# quantizer_control.net
KiCad netlist of a schematic drawn in EAGLE
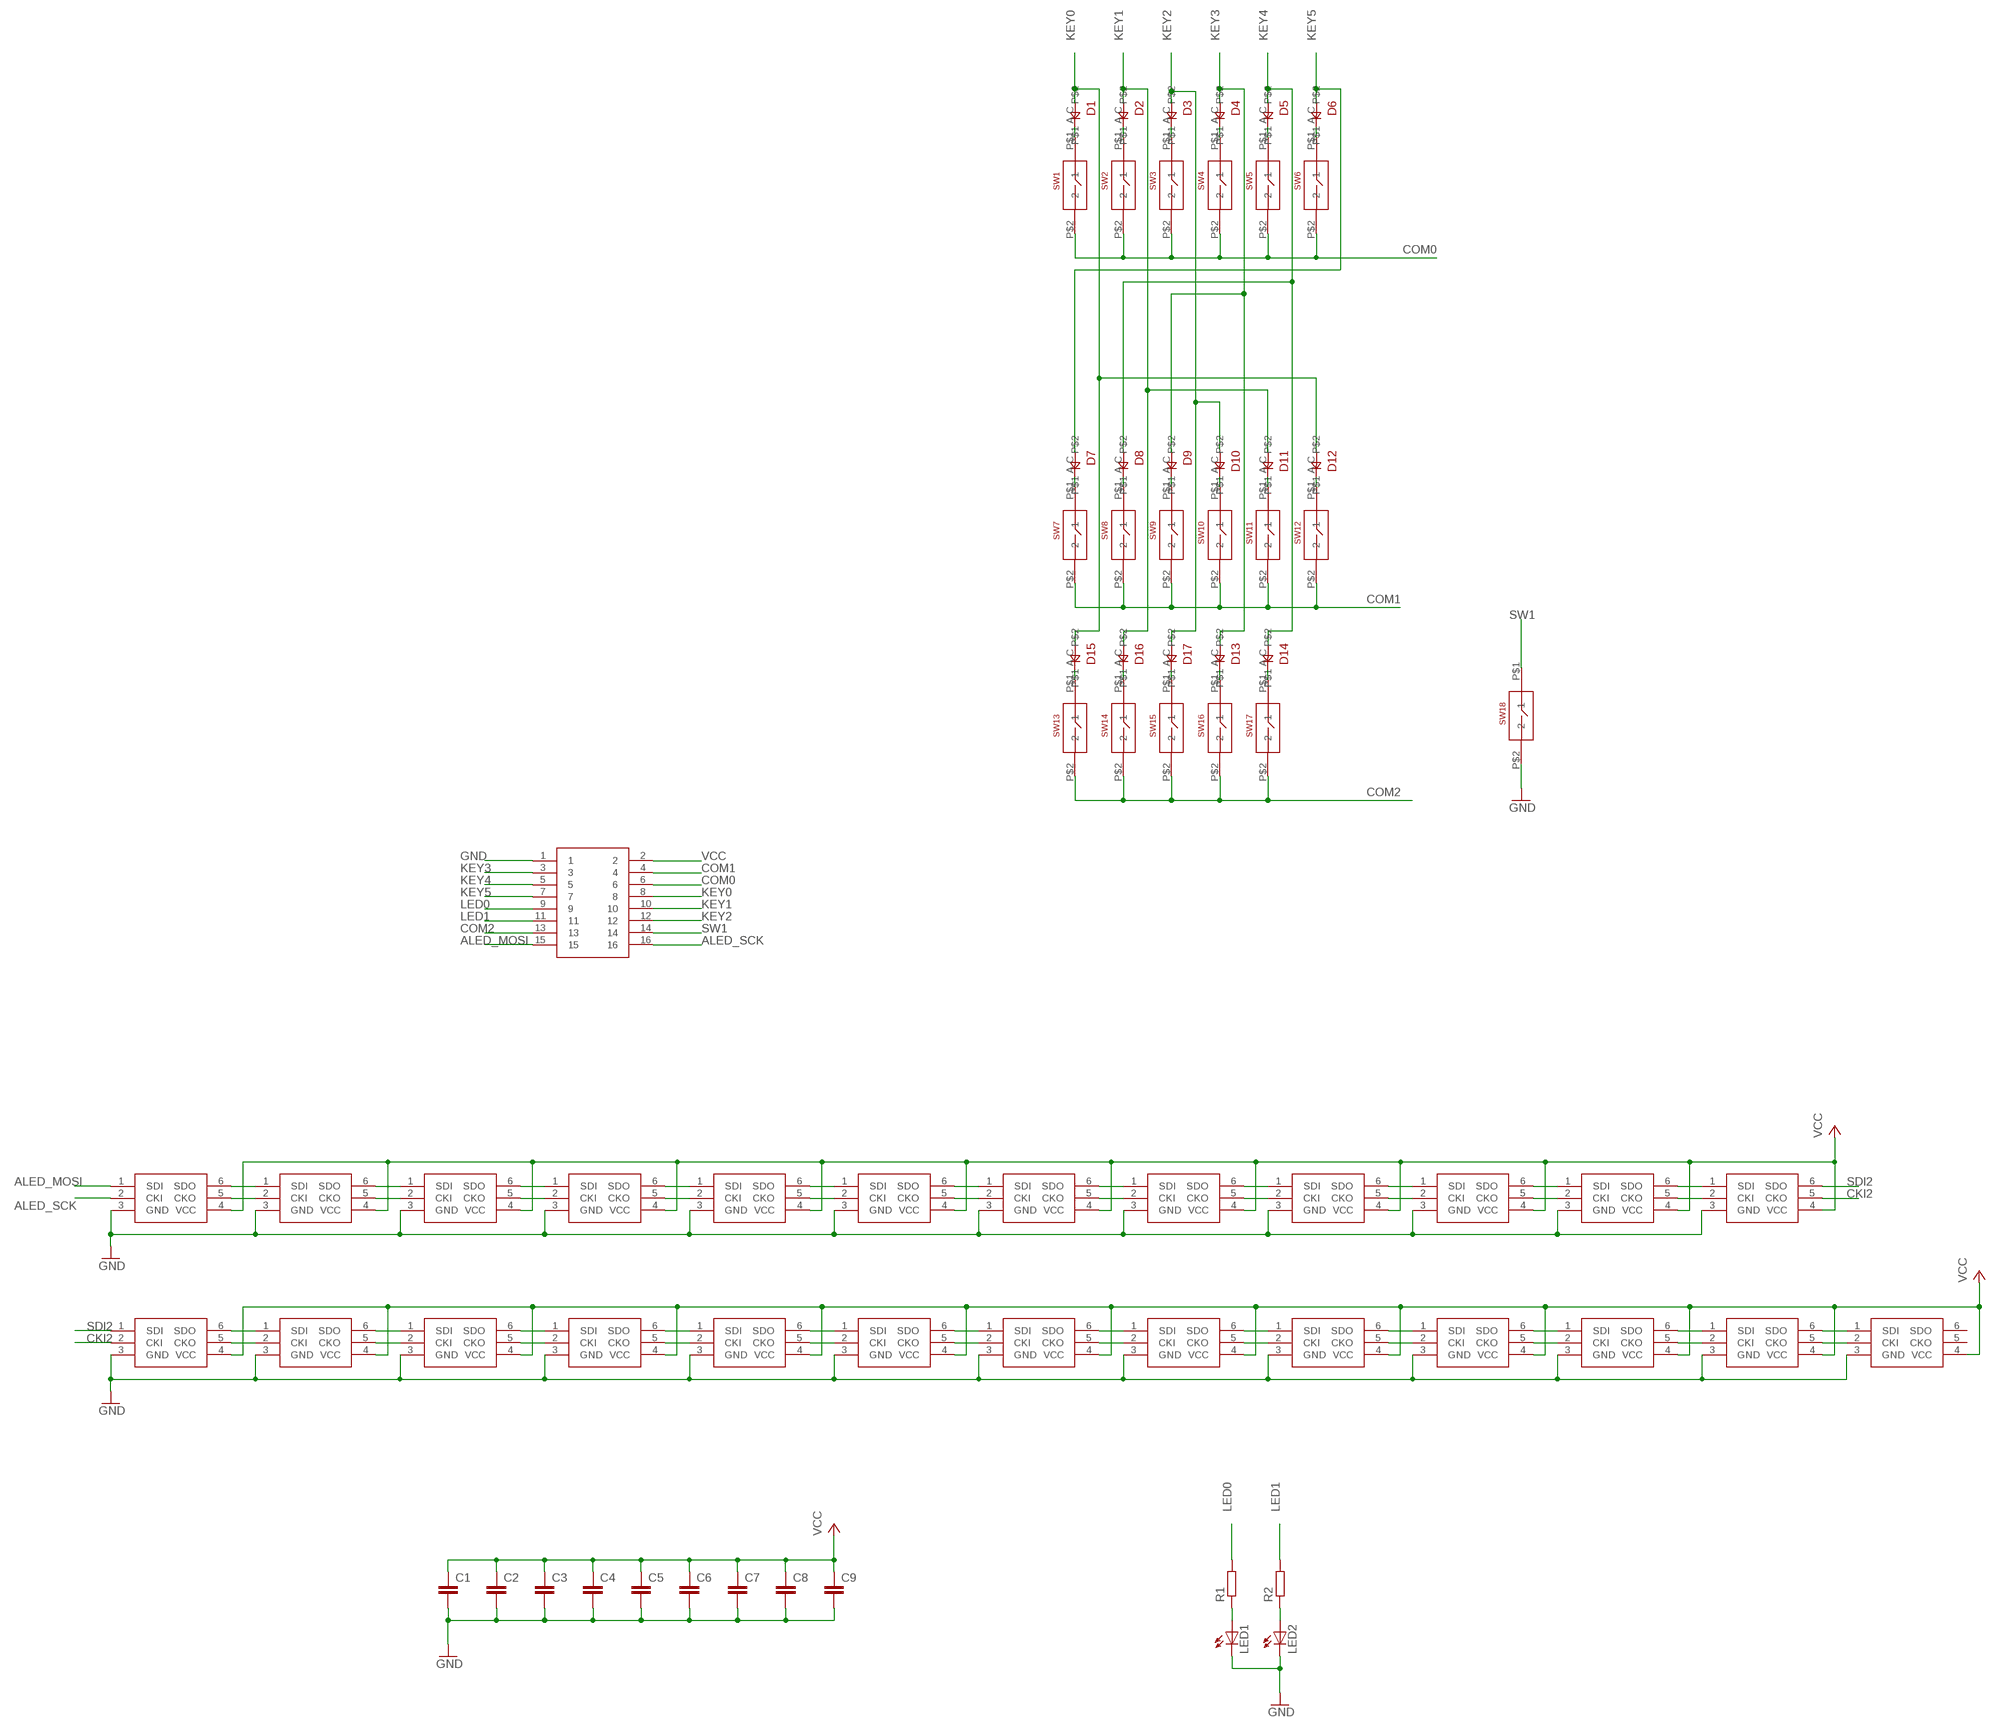
[diagram p0: schematic, sheet 1]

(export (version "E")
  (design (tool "Eeschema 10.0.6"))
  (components
    (comp (ref "C1")
      (value "C-EUC0805")
      (footprint "eagle-import:C0805")
      (libsource (lib "eagle-import") (part "C-EUC0805"))
    )
    (comp (ref "C2")
      (value "C-EUC0805")
      (footprint "eagle-import:C0805")
      (libsource (lib "eagle-import") (part "C-EUC0805"))
    )
    (comp (ref "C3")
      (value "C-EUC0805")
      (footprint "eagle-import:C0805")
      (libsource (lib "eagle-import") (part "C-EUC0805"))
    )
    (comp (ref "C4")
      (value "C-EUC0805")
      (footprint "eagle-import:C0805")
      (libsource (lib "eagle-import") (part "C-EUC0805"))
    )
    (comp (ref "C5")
      (value "C-EUC0805")
      (footprint "eagle-import:C0805")
      (libsource (lib "eagle-import") (part "C-EUC0805"))
    )
    (comp (ref "C6")
      (value "C-EUC0805")
      (footprint "eagle-import:C0805")
      (libsource (lib "eagle-import") (part "C-EUC0805"))
    )
    (comp (ref "C7")
      (value "C-EUC0805")
      (footprint "eagle-import:C0805")
      (libsource (lib "eagle-import") (part "C-EUC0805"))
    )
    (comp (ref "C8")
      (value "C-EUC0805")
      (footprint "eagle-import:C0805")
      (libsource (lib "eagle-import") (part "C-EUC0805"))
    )
    (comp (ref "C9")
      (value "C-EUC0805")
      (footprint "eagle-import:C0805")
      (libsource (lib "eagle-import") (part "C-EUC0805"))
    )
    (comp (ref "D1")
      (value "0805DIODE")
      (footprint "eagle-import:0805DIODE")
      (libsource (lib "eagle-import") (part "0805DIODE"))
    )
    (comp (ref "D2")
      (value "0805DIODE")
      (footprint "eagle-import:0805DIODE")
      (libsource (lib "eagle-import") (part "0805DIODE"))
    )
    (comp (ref "D3")
      (value "0805DIODE")
      (footprint "eagle-import:0805DIODE")
      (libsource (lib "eagle-import") (part "0805DIODE"))
    )
    (comp (ref "D4")
      (value "0805DIODE")
      (footprint "eagle-import:0805DIODE")
      (libsource (lib "eagle-import") (part "0805DIODE"))
    )
    (comp (ref "D5")
      (value "0805DIODE")
      (footprint "eagle-import:0805DIODE")
      (libsource (lib "eagle-import") (part "0805DIODE"))
    )
    (comp (ref "D6")
      (value "0805DIODE")
      (footprint "eagle-import:0805DIODE")
      (libsource (lib "eagle-import") (part "0805DIODE"))
    )
    (comp (ref "D7")
      (value "0805DIODE")
      (footprint "eagle-import:0805DIODE")
      (libsource (lib "eagle-import") (part "0805DIODE"))
    )
    (comp (ref "D8")
      (value "0805DIODE")
      (footprint "eagle-import:0805DIODE")
      (libsource (lib "eagle-import") (part "0805DIODE"))
    )
    (comp (ref "D9")
      (value "0805DIODE")
      (footprint "eagle-import:0805DIODE")
      (libsource (lib "eagle-import") (part "0805DIODE"))
    )
    (comp (ref "D10")
      (value "0805DIODE")
      (footprint "eagle-import:0805DIODE")
      (libsource (lib "eagle-import") (part "0805DIODE"))
    )
    (comp (ref "D11")
      (value "0805DIODE")
      (footprint "eagle-import:0805DIODE")
      (libsource (lib "eagle-import") (part "0805DIODE"))
    )
    (comp (ref "D12")
      (value "0805DIODE")
      (footprint "eagle-import:0805DIODE")
      (libsource (lib "eagle-import") (part "0805DIODE"))
    )
    (comp (ref "D13")
      (value "0805DIODE")
      (footprint "eagle-import:0805DIODE")
      (libsource (lib "eagle-import") (part "0805DIODE"))
    )
    (comp (ref "D14")
      (value "0805DIODE")
      (footprint "eagle-import:0805DIODE")
      (libsource (lib "eagle-import") (part "0805DIODE"))
    )
    (comp (ref "D15")
      (value "0805DIODE")
      (footprint "eagle-import:0805DIODE")
      (libsource (lib "eagle-import") (part "0805DIODE"))
    )
    (comp (ref "D16")
      (value "0805DIODE")
      (footprint "eagle-import:0805DIODE")
      (libsource (lib "eagle-import") (part "0805DIODE"))
    )
    (comp (ref "D17")
      (value "0805DIODE")
      (footprint "eagle-import:0805DIODE")
      (libsource (lib "eagle-import") (part "0805DIODE"))
    )
    (comp (ref "LED1")
      (value "LEDCHIP-LED0805")
      (footprint "eagle-import:CHIP-LED0805")
      (libsource (lib "eagle-import") (part "LEDCHIP-LED0805"))
    )
    (comp (ref "LED2")
      (value "LEDCHIP-LED0805")
      (footprint "eagle-import:CHIP-LED0805")
      (libsource (lib "eagle-import") (part "LEDCHIP-LED0805"))
    )
    (comp (ref "R1")
      (value "R-EU_R0805")
      (footprint "eagle-import:R0805")
      (libsource (lib "eagle-import") (part "R-EU_R0805"))
    )
    (comp (ref "R2")
      (value "R-EU_R0805")
      (footprint "eagle-import:R0805")
      (libsource (lib "eagle-import") (part "R-EU_R0805"))
    )
    (comp (ref "SW1")
      (value "SKPMSWITCH")
      (footprint "eagle-import:SKPMSWITCH")
      (libsource (lib "eagle-import") (part "SKPMSWITCH"))
    )
    (comp (ref "SW2")
      (value "SKPMSWITCH")
      (footprint "eagle-import:SKPMSWITCH")
      (libsource (lib "eagle-import") (part "SKPMSWITCH"))
    )
    (comp (ref "SW3")
      (value "SKPMSWITCH")
      (footprint "eagle-import:SKPMSWITCH")
      (libsource (lib "eagle-import") (part "SKPMSWITCH"))
    )
    (comp (ref "SW4")
      (value "SKPMSWITCH")
      (footprint "eagle-import:SKPMSWITCH")
      (libsource (lib "eagle-import") (part "SKPMSWITCH"))
    )
    (comp (ref "SW5")
      (value "SKPMSWITCH")
      (footprint "eagle-import:SKPMSWITCH")
      (libsource (lib "eagle-import") (part "SKPMSWITCH"))
    )
    (comp (ref "SW6")
      (value "SKPMSWITCH")
      (footprint "eagle-import:SKPMSWITCH")
      (libsource (lib "eagle-import") (part "SKPMSWITCH"))
    )
    (comp (ref "SW7")
      (value "SKPMSWITCH")
      (footprint "eagle-import:SKPMSWITCH")
      (libsource (lib "eagle-import") (part "SKPMSWITCH"))
    )
    (comp (ref "SW8")
      (value "SKPMSWITCH")
      (footprint "eagle-import:SKPMSWITCH")
      (libsource (lib "eagle-import") (part "SKPMSWITCH"))
    )
    (comp (ref "SW9")
      (value "SKPMSWITCH")
      (footprint "eagle-import:SKPMSWITCH")
      (libsource (lib "eagle-import") (part "SKPMSWITCH"))
    )
    (comp (ref "SW10")
      (value "SKPMSWITCH")
      (footprint "eagle-import:SKPMSWITCH")
      (libsource (lib "eagle-import") (part "SKPMSWITCH"))
    )
    (comp (ref "SW11")
      (value "SKPMSWITCH")
      (footprint "eagle-import:SKPMSWITCH")
      (libsource (lib "eagle-import") (part "SKPMSWITCH"))
    )
    (comp (ref "SW12")
      (value "SKPMSWITCH")
      (footprint "eagle-import:SKPMSWITCH")
      (libsource (lib "eagle-import") (part "SKPMSWITCH"))
    )
    (comp (ref "SW13")
      (value "SKPMSWITCH")
      (footprint "eagle-import:SKPMSWITCH")
      (libsource (lib "eagle-import") (part "SKPMSWITCH"))
    )
    (comp (ref "SW14")
      (value "SKPMSWITCH")
      (footprint "eagle-import:SKPMSWITCH")
      (libsource (lib "eagle-import") (part "SKPMSWITCH"))
    )
    (comp (ref "SW15")
      (value "SKPMSWITCH")
      (footprint "eagle-import:SKPMSWITCH")
      (libsource (lib "eagle-import") (part "SKPMSWITCH"))
    )
    (comp (ref "SW16")
      (value "SKPMSWITCH")
      (footprint "eagle-import:SKPMSWITCH")
      (libsource (lib "eagle-import") (part "SKPMSWITCH"))
    )
    (comp (ref "SW17")
      (value "SKPMSWITCH")
      (footprint "eagle-import:SKPMSWITCH")
      (libsource (lib "eagle-import") (part "SKPMSWITCH"))
    )
    (comp (ref "SW18")
      (value "SKPMSWITCH")
      (footprint "eagle-import:SKPMSWITCH")
      (libsource (lib "eagle-import") (part "SKPMSWITCH"))
    )
    (comp (ref "U$1")
      (value "2X8SMT")
      (footprint "eagle-import:2X8-SMT")
      (libsource (lib "eagle-import") (part "2X8SMT"))
    )
    (comp (ref "U$2")
      (value "APA102-2020")
      (footprint "eagle-import:APA102-2020")
      (libsource (lib "eagle-import") (part "APA102-2020"))
    )
    (comp (ref "U$3")
      (value "APA102-2020")
      (footprint "eagle-import:APA102-2020")
      (libsource (lib "eagle-import") (part "APA102-2020"))
    )
    (comp (ref "U$4")
      (value "APA102-2020")
      (footprint "eagle-import:APA102-2020")
      (libsource (lib "eagle-import") (part "APA102-2020"))
    )
    (comp (ref "U$5")
      (value "APA102-2020")
      (footprint "eagle-import:APA102-2020")
      (libsource (lib "eagle-import") (part "APA102-2020"))
    )
    (comp (ref "U$6")
      (value "APA102-2020")
      (footprint "eagle-import:APA102-2020")
      (libsource (lib "eagle-import") (part "APA102-2020"))
    )
    (comp (ref "U$7")
      (value "APA102-2020")
      (footprint "eagle-import:APA102-2020")
      (libsource (lib "eagle-import") (part "APA102-2020"))
    )
    (comp (ref "U$8")
      (value "APA102-2020")
      (footprint "eagle-import:APA102-2020")
      (libsource (lib "eagle-import") (part "APA102-2020"))
    )
    (comp (ref "U$9")
      (value "APA102-2020")
      (footprint "eagle-import:APA102-2020")
      (libsource (lib "eagle-import") (part "APA102-2020"))
    )
    (comp (ref "U$10")
      (value "APA102-2020")
      (footprint "eagle-import:APA102-2020")
      (libsource (lib "eagle-import") (part "APA102-2020"))
    )
    (comp (ref "U$11")
      (value "APA102-2020")
      (footprint "eagle-import:APA102-2020")
      (libsource (lib "eagle-import") (part "APA102-2020"))
    )
    (comp (ref "U$13")
      (value "APA102-2020")
      (footprint "eagle-import:APA102-2020")
      (libsource (lib "eagle-import") (part "APA102-2020"))
    )
    (comp (ref "U$14")
      (value "APA102-2020")
      (footprint "eagle-import:APA102-2020")
      (libsource (lib "eagle-import") (part "APA102-2020"))
    )
    (comp (ref "U$15")
      (value "APA102-2020")
      (footprint "eagle-import:APA102-2020")
      (libsource (lib "eagle-import") (part "APA102-2020"))
    )
    (comp (ref "U$16")
      (value "APA102-2020")
      (footprint "eagle-import:APA102-2020")
      (libsource (lib "eagle-import") (part "APA102-2020"))
    )
    (comp (ref "U$17")
      (value "APA102-2020")
      (footprint "eagle-import:APA102-2020")
      (libsource (lib "eagle-import") (part "APA102-2020"))
    )
    (comp (ref "U$18")
      (value "APA102-2020")
      (footprint "eagle-import:APA102-2020")
      (libsource (lib "eagle-import") (part "APA102-2020"))
    )
    (comp (ref "U$19")
      (value "APA102-2020")
      (footprint "eagle-import:APA102-2020")
      (libsource (lib "eagle-import") (part "APA102-2020"))
    )
    (comp (ref "U$20")
      (value "APA102-2020")
      (footprint "eagle-import:APA102-2020")
      (libsource (lib "eagle-import") (part "APA102-2020"))
    )
    (comp (ref "U$21")
      (value "APA102-2020")
      (footprint "eagle-import:APA102-2020")
      (libsource (lib "eagle-import") (part "APA102-2020"))
    )
    (comp (ref "U$22")
      (value "APA102-2020")
      (footprint "eagle-import:APA102-2020")
      (libsource (lib "eagle-import") (part "APA102-2020"))
    )
    (comp (ref "U$23")
      (value "APA102-2020")
      (footprint "eagle-import:APA102-2020")
      (libsource (lib "eagle-import") (part "APA102-2020"))
    )
    (comp (ref "U$24")
      (value "APA102-2020")
      (footprint "eagle-import:APA102-2020")
      (libsource (lib "eagle-import") (part "APA102-2020"))
    )
    (comp (ref "U$25")
      (value "APA102-2020")
      (footprint "eagle-import:APA102-2020")
      (libsource (lib "eagle-import") (part "APA102-2020"))
    )
    (comp (ref "U$26")
      (value "APA102-2020")
      (footprint "eagle-import:APA102-2020")
      (libsource (lib "eagle-import") (part "APA102-2020"))
    )
    (comp (ref "U$27")
      (value "APA102-2020")
      (footprint "eagle-import:APA102-2020")
      (libsource (lib "eagle-import") (part "APA102-2020"))
    )
  )
  (nets
    (net (code "1") (name "/ALED_MOSI") (class "Default")
      (node (ref "U$1") (pin "15") (pinfunction "15_15") (pintype "bidirectional"))
      (node (ref "U$2") (pin "1") (pinfunction "SDI_1") (pintype "bidirectional"))
    )
    (net (code "2") (name "/ALED_SCK") (class "Default")
      (node (ref "U$1") (pin "16") (pinfunction "16_16") (pintype "bidirectional"))
      (node (ref "U$2") (pin "2") (pinfunction "CKI_2") (pintype "bidirectional"))
    )
    (net (code "3") (name "/CKI2") (class "Default")
      (node (ref "U$14") (pin "5") (pinfunction "CKO_5") (pintype "bidirectional"))
      (node (ref "U$15") (pin "2") (pinfunction "CKI_2") (pintype "bidirectional"))
    )
    (net (code "4") (name "/COM0") (class "Default")
      (node (ref "SW1") (pin "P$2") (pinfunction "2_P$2") (pintype "bidirectional"))
      (node (ref "SW2") (pin "P$2") (pinfunction "2_P$2") (pintype "bidirectional"))
      (node (ref "SW3") (pin "P$2") (pinfunction "2_P$2") (pintype "bidirectional"))
      (node (ref "SW4") (pin "P$2") (pinfunction "2_P$2") (pintype "bidirectional"))
      (node (ref "SW5") (pin "P$2") (pinfunction "2_P$2") (pintype "bidirectional"))
      (node (ref "SW6") (pin "P$2") (pinfunction "2_P$2") (pintype "bidirectional"))
      (node (ref "U$1") (pin "6") (pinfunction "6_6") (pintype "bidirectional"))
    )
    (net (code "5") (name "/COM1") (class "Default")
      (node (ref "SW10") (pin "P$2") (pinfunction "2_P$2") (pintype "bidirectional"))
      (node (ref "SW11") (pin "P$2") (pinfunction "2_P$2") (pintype "bidirectional"))
      (node (ref "SW12") (pin "P$2") (pinfunction "2_P$2") (pintype "bidirectional"))
      (node (ref "SW7") (pin "P$2") (pinfunction "2_P$2") (pintype "bidirectional"))
      (node (ref "SW8") (pin "P$2") (pinfunction "2_P$2") (pintype "bidirectional"))
      (node (ref "SW9") (pin "P$2") (pinfunction "2_P$2") (pintype "bidirectional"))
      (node (ref "U$1") (pin "4") (pinfunction "4_4") (pintype "bidirectional"))
    )
    (net (code "6") (name "/COM2") (class "Default")
      (node (ref "SW13") (pin "P$2") (pinfunction "2_P$2") (pintype "bidirectional"))
      (node (ref "SW14") (pin "P$2") (pinfunction "2_P$2") (pintype "bidirectional"))
      (node (ref "SW15") (pin "P$2") (pinfunction "2_P$2") (pintype "bidirectional"))
      (node (ref "SW16") (pin "P$2") (pinfunction "2_P$2") (pintype "bidirectional"))
      (node (ref "SW17") (pin "P$2") (pinfunction "2_P$2") (pintype "bidirectional"))
      (node (ref "U$1") (pin "13") (pinfunction "13_13") (pintype "bidirectional"))
    )
    (net (code "7") (name "/KEY0") (class "Default")
      (node (ref "D1") (pin "C") (pinfunction "P$1_C") (pintype "bidirectional"))
      (node (ref "D12") (pin "C") (pinfunction "P$1_C") (pintype "bidirectional"))
      (node (ref "D15") (pin "C") (pinfunction "P$1_C") (pintype "bidirectional"))
      (node (ref "U$1") (pin "8") (pinfunction "8_8") (pintype "bidirectional"))
    )
    (net (code "8") (name "/KEY1") (class "Default")
      (node (ref "D11") (pin "C") (pinfunction "P$1_C") (pintype "bidirectional"))
      (node (ref "D16") (pin "C") (pinfunction "P$1_C") (pintype "bidirectional"))
      (node (ref "D2") (pin "C") (pinfunction "P$1_C") (pintype "bidirectional"))
      (node (ref "U$1") (pin "10") (pinfunction "10_10") (pintype "bidirectional"))
    )
    (net (code "9") (name "/KEY2") (class "Default")
      (node (ref "D10") (pin "C") (pinfunction "P$1_C") (pintype "bidirectional"))
      (node (ref "D17") (pin "C") (pinfunction "P$1_C") (pintype "bidirectional"))
      (node (ref "D3") (pin "C") (pinfunction "P$1_C") (pintype "bidirectional"))
      (node (ref "U$1") (pin "12") (pinfunction "12_12") (pintype "bidirectional"))
    )
    (net (code "10") (name "/KEY3") (class "Default")
      (node (ref "D13") (pin "C") (pinfunction "P$1_C") (pintype "bidirectional"))
      (node (ref "D4") (pin "C") (pinfunction "P$1_C") (pintype "bidirectional"))
      (node (ref "D9") (pin "C") (pinfunction "P$1_C") (pintype "bidirectional"))
      (node (ref "U$1") (pin "3") (pinfunction "3_3") (pintype "bidirectional"))
    )
    (net (code "11") (name "/KEY4") (class "Default")
      (node (ref "D14") (pin "C") (pinfunction "P$1_C") (pintype "bidirectional"))
      (node (ref "D5") (pin "C") (pinfunction "P$1_C") (pintype "bidirectional"))
      (node (ref "D8") (pin "C") (pinfunction "P$1_C") (pintype "bidirectional"))
      (node (ref "U$1") (pin "5") (pinfunction "5_5") (pintype "bidirectional"))
    )
    (net (code "12") (name "/KEY5") (class "Default")
      (node (ref "D6") (pin "C") (pinfunction "P$1_C") (pintype "bidirectional"))
      (node (ref "D7") (pin "C") (pinfunction "P$1_C") (pintype "bidirectional"))
      (node (ref "U$1") (pin "7") (pinfunction "7_7") (pintype "bidirectional"))
    )
    (net (code "13") (name "/LED0") (class "Default")
      (node (ref "R1") (pin "2") (pinfunction "2_2") (pintype "passive"))
      (node (ref "U$1") (pin "9") (pinfunction "9_9") (pintype "bidirectional"))
    )
    (net (code "14") (name "/LED1") (class "Default")
      (node (ref "R2") (pin "2") (pinfunction "2_2") (pintype "passive"))
      (node (ref "U$1") (pin "11") (pinfunction "11_11") (pintype "bidirectional"))
    )
    (net (code "15") (name "/SDI2") (class "Default")
      (node (ref "U$14") (pin "6") (pinfunction "SDO_6") (pintype "bidirectional"))
      (node (ref "U$15") (pin "1") (pinfunction "SDI_1") (pintype "bidirectional"))
    )
    (net (code "16") (name "/SW1") (class "Default")
      (node (ref "SW18") (pin "P$1") (pinfunction "1_P$1") (pintype "bidirectional"))
      (node (ref "U$1") (pin "14") (pinfunction "14_14") (pintype "bidirectional"))
    )
    (net (code "17") (name "GND") (class "Default")
      (node (ref "C1") (pin "2") (pinfunction "2_2") (pintype "passive"))
      (node (ref "C2") (pin "2") (pinfunction "2_2") (pintype "passive"))
      (node (ref "C3") (pin "2") (pinfunction "2_2") (pintype "passive"))
      (node (ref "C4") (pin "2") (pinfunction "2_2") (pintype "passive"))
      (node (ref "C5") (pin "2") (pinfunction "2_2") (pintype "passive"))
      (node (ref "C6") (pin "2") (pinfunction "2_2") (pintype "passive"))
      (node (ref "C7") (pin "2") (pinfunction "2_2") (pintype "passive"))
      (node (ref "C8") (pin "2") (pinfunction "2_2") (pintype "passive"))
      (node (ref "C9") (pin "2") (pinfunction "2_2") (pintype "passive"))
      (node (ref "LED1") (pin "C") (pinfunction "C_C") (pintype "passive"))
      (node (ref "LED2") (pin "C") (pinfunction "C_C") (pintype "passive"))
      (node (ref "SW18") (pin "P$2") (pinfunction "2_P$2") (pintype "bidirectional"))
      (node (ref "U$1") (pin "1") (pinfunction "1_1") (pintype "bidirectional"))
      (node (ref "U$10") (pin "3") (pinfunction "GND_3") (pintype "power_in"))
      (node (ref "U$11") (pin "3") (pinfunction "GND_3") (pintype "power_in"))
      (node (ref "U$13") (pin "3") (pinfunction "GND_3") (pintype "power_in"))
      (node (ref "U$14") (pin "3") (pinfunction "GND_3") (pintype "power_in"))
      (node (ref "U$15") (pin "3") (pinfunction "GND_3") (pintype "power_in"))
      (node (ref "U$16") (pin "3") (pinfunction "GND_3") (pintype "power_in"))
      (node (ref "U$17") (pin "3") (pinfunction "GND_3") (pintype "power_in"))
      (node (ref "U$18") (pin "3") (pinfunction "GND_3") (pintype "power_in"))
      (node (ref "U$19") (pin "3") (pinfunction "GND_3") (pintype "power_in"))
      (node (ref "U$2") (pin "3") (pinfunction "GND_3") (pintype "power_in"))
      (node (ref "U$20") (pin "3") (pinfunction "GND_3") (pintype "power_in"))
      (node (ref "U$21") (pin "3") (pinfunction "GND_3") (pintype "power_in"))
      (node (ref "U$22") (pin "3") (pinfunction "GND_3") (pintype "power_in"))
      (node (ref "U$23") (pin "3") (pinfunction "GND_3") (pintype "power_in"))
      (node (ref "U$24") (pin "3") (pinfunction "GND_3") (pintype "power_in"))
      (node (ref "U$25") (pin "3") (pinfunction "GND_3") (pintype "power_in"))
      (node (ref "U$26") (pin "3") (pinfunction "GND_3") (pintype "power_in"))
      (node (ref "U$27") (pin "3") (pinfunction "GND_3") (pintype "power_in"))
      (node (ref "U$3") (pin "3") (pinfunction "GND_3") (pintype "power_in"))
      (node (ref "U$4") (pin "3") (pinfunction "GND_3") (pintype "power_in"))
      (node (ref "U$5") (pin "3") (pinfunction "GND_3") (pintype "power_in"))
      (node (ref "U$6") (pin "3") (pinfunction "GND_3") (pintype "power_in"))
      (node (ref "U$7") (pin "3") (pinfunction "GND_3") (pintype "power_in"))
      (node (ref "U$8") (pin "3") (pinfunction "GND_3") (pintype "power_in"))
      (node (ref "U$9") (pin "3") (pinfunction "GND_3") (pintype "power_in"))
    )
    (net (code "18") (name "Net-(D1-P$2)") (class "Default")
      (node (ref "D1") (pin "A") (pinfunction "P$2_A") (pintype "bidirectional"))
      (node (ref "SW1") (pin "P$1") (pinfunction "1_P$1") (pintype "bidirectional"))
    )
    (net (code "19") (name "Net-(D2-P$2)") (class "Default")
      (node (ref "D2") (pin "A") (pinfunction "P$2_A") (pintype "bidirectional"))
      (node (ref "SW2") (pin "P$1") (pinfunction "1_P$1") (pintype "bidirectional"))
    )
    (net (code "20") (name "Net-(D3-P$2)") (class "Default")
      (node (ref "D3") (pin "A") (pinfunction "P$2_A") (pintype "bidirectional"))
      (node (ref "SW3") (pin "P$1") (pinfunction "1_P$1") (pintype "bidirectional"))
    )
    (net (code "21") (name "Net-(D4-P$2)") (class "Default")
      (node (ref "D4") (pin "A") (pinfunction "P$2_A") (pintype "bidirectional"))
      (node (ref "SW4") (pin "P$1") (pinfunction "1_P$1") (pintype "bidirectional"))
    )
    (net (code "22") (name "Net-(D5-P$2)") (class "Default")
      (node (ref "D5") (pin "A") (pinfunction "P$2_A") (pintype "bidirectional"))
      (node (ref "SW5") (pin "P$1") (pinfunction "1_P$1") (pintype "bidirectional"))
    )
    (net (code "23") (name "Net-(D6-P$2)") (class "Default")
      (node (ref "D6") (pin "A") (pinfunction "P$2_A") (pintype "bidirectional"))
      (node (ref "SW6") (pin "P$1") (pinfunction "1_P$1") (pintype "bidirectional"))
    )
    (net (code "24") (name "Net-(D7-P$2)") (class "Default")
      (node (ref "D7") (pin "A") (pinfunction "P$2_A") (pintype "bidirectional"))
      (node (ref "SW7") (pin "P$1") (pinfunction "1_P$1") (pintype "bidirectional"))
    )
    (net (code "25") (name "Net-(D8-P$2)") (class "Default")
      (node (ref "D8") (pin "A") (pinfunction "P$2_A") (pintype "bidirectional"))
      (node (ref "SW8") (pin "P$1") (pinfunction "1_P$1") (pintype "bidirectional"))
    )
    (net (code "26") (name "Net-(D9-P$2)") (class "Default")
      (node (ref "D9") (pin "A") (pinfunction "P$2_A") (pintype "bidirectional"))
      (node (ref "SW9") (pin "P$1") (pinfunction "1_P$1") (pintype "bidirectional"))
    )
    (net (code "27") (name "Net-(D10-P$2)") (class "Default")
      (node (ref "D10") (pin "A") (pinfunction "P$2_A") (pintype "bidirectional"))
      (node (ref "SW10") (pin "P$1") (pinfunction "1_P$1") (pintype "bidirectional"))
    )
    (net (code "28") (name "Net-(D11-P$2)") (class "Default")
      (node (ref "D11") (pin "A") (pinfunction "P$2_A") (pintype "bidirectional"))
      (node (ref "SW11") (pin "P$1") (pinfunction "1_P$1") (pintype "bidirectional"))
    )
    (net (code "29") (name "Net-(D12-P$2)") (class "Default")
      (node (ref "D12") (pin "A") (pinfunction "P$2_A") (pintype "bidirectional"))
      (node (ref "SW12") (pin "P$1") (pinfunction "1_P$1") (pintype "bidirectional"))
    )
    (net (code "30") (name "Net-(D13-P$2)") (class "Default")
      (node (ref "D13") (pin "A") (pinfunction "P$2_A") (pintype "bidirectional"))
      (node (ref "SW16") (pin "P$1") (pinfunction "1_P$1") (pintype "bidirectional"))
    )
    (net (code "31") (name "Net-(D14-P$2)") (class "Default")
      (node (ref "D14") (pin "A") (pinfunction "P$2_A") (pintype "bidirectional"))
      (node (ref "SW17") (pin "P$1") (pinfunction "1_P$1") (pintype "bidirectional"))
    )
    (net (code "32") (name "Net-(D15-P$2)") (class "Default")
      (node (ref "D15") (pin "A") (pinfunction "P$2_A") (pintype "bidirectional"))
      (node (ref "SW13") (pin "P$1") (pinfunction "1_P$1") (pintype "bidirectional"))
    )
    (net (code "33") (name "Net-(D16-P$2)") (class "Default")
      (node (ref "D16") (pin "A") (pinfunction "P$2_A") (pintype "bidirectional"))
      (node (ref "SW14") (pin "P$1") (pinfunction "1_P$1") (pintype "bidirectional"))
    )
    (net (code "34") (name "Net-(D17-P$2)") (class "Default")
      (node (ref "D17") (pin "A") (pinfunction "P$2_A") (pintype "bidirectional"))
      (node (ref "SW15") (pin "P$1") (pinfunction "1_P$1") (pintype "bidirectional"))
    )
    (net (code "35") (name "Net-(LED1-PadA)") (class "Default")
      (node (ref "LED1") (pin "A") (pinfunction "A_A") (pintype "passive"))
      (node (ref "R1") (pin "1") (pinfunction "1_1") (pintype "passive"))
    )
    (net (code "36") (name "Net-(LED2-PadA)") (class "Default")
      (node (ref "LED2") (pin "A") (pinfunction "A_A") (pintype "passive"))
      (node (ref "R2") (pin "1") (pinfunction "1_1") (pintype "passive"))
    )
    (net (code "37") (name "Net-(U$2-CKO)") (class "Default")
      (node (ref "U$2") (pin "5") (pinfunction "CKO_5") (pintype "bidirectional"))
      (node (ref "U$3") (pin "2") (pinfunction "CKI_2") (pintype "bidirectional"))
    )
    (net (code "38") (name "Net-(U$2-SDO)") (class "Default")
      (node (ref "U$2") (pin "6") (pinfunction "SDO_6") (pintype "bidirectional"))
      (node (ref "U$3") (pin "1") (pinfunction "SDI_1") (pintype "bidirectional"))
    )
    (net (code "39") (name "Net-(U$3-CKO)") (class "Default")
      (node (ref "U$3") (pin "5") (pinfunction "CKO_5") (pintype "bidirectional"))
      (node (ref "U$4") (pin "2") (pinfunction "CKI_2") (pintype "bidirectional"))
    )
    (net (code "40") (name "Net-(U$3-SDO)") (class "Default")
      (node (ref "U$3") (pin "6") (pinfunction "SDO_6") (pintype "bidirectional"))
      (node (ref "U$4") (pin "1") (pinfunction "SDI_1") (pintype "bidirectional"))
    )
    (net (code "41") (name "Net-(U$4-CKO)") (class "Default")
      (node (ref "U$4") (pin "5") (pinfunction "CKO_5") (pintype "bidirectional"))
      (node (ref "U$5") (pin "2") (pinfunction "CKI_2") (pintype "bidirectional"))
    )
    (net (code "42") (name "Net-(U$4-SDO)") (class "Default")
      (node (ref "U$4") (pin "6") (pinfunction "SDO_6") (pintype "bidirectional"))
      (node (ref "U$5") (pin "1") (pinfunction "SDI_1") (pintype "bidirectional"))
    )
    (net (code "43") (name "Net-(U$5-CKO)") (class "Default")
      (node (ref "U$5") (pin "5") (pinfunction "CKO_5") (pintype "bidirectional"))
      (node (ref "U$6") (pin "2") (pinfunction "CKI_2") (pintype "bidirectional"))
    )
    (net (code "44") (name "Net-(U$5-SDO)") (class "Default")
      (node (ref "U$5") (pin "6") (pinfunction "SDO_6") (pintype "bidirectional"))
      (node (ref "U$6") (pin "1") (pinfunction "SDI_1") (pintype "bidirectional"))
    )
    (net (code "45") (name "Net-(U$6-CKO)") (class "Default")
      (node (ref "U$6") (pin "5") (pinfunction "CKO_5") (pintype "bidirectional"))
      (node (ref "U$7") (pin "2") (pinfunction "CKI_2") (pintype "bidirectional"))
    )
    (net (code "46") (name "Net-(U$6-SDO)") (class "Default")
      (node (ref "U$6") (pin "6") (pinfunction "SDO_6") (pintype "bidirectional"))
      (node (ref "U$7") (pin "1") (pinfunction "SDI_1") (pintype "bidirectional"))
    )
    (net (code "47") (name "Net-(U$7-CKO)") (class "Default")
      (node (ref "U$7") (pin "5") (pinfunction "CKO_5") (pintype "bidirectional"))
      (node (ref "U$8") (pin "2") (pinfunction "CKI_2") (pintype "bidirectional"))
    )
    (net (code "48") (name "Net-(U$7-SDO)") (class "Default")
      (node (ref "U$7") (pin "6") (pinfunction "SDO_6") (pintype "bidirectional"))
      (node (ref "U$8") (pin "1") (pinfunction "SDI_1") (pintype "bidirectional"))
    )
    (net (code "49") (name "Net-(U$8-CKO)") (class "Default")
      (node (ref "U$8") (pin "5") (pinfunction "CKO_5") (pintype "bidirectional"))
      (node (ref "U$9") (pin "2") (pinfunction "CKI_2") (pintype "bidirectional"))
    )
    (net (code "50") (name "Net-(U$8-SDO)") (class "Default")
      (node (ref "U$8") (pin "6") (pinfunction "SDO_6") (pintype "bidirectional"))
      (node (ref "U$9") (pin "1") (pinfunction "SDI_1") (pintype "bidirectional"))
    )
    (net (code "51") (name "Net-(U$10-CKI)") (class "Default")
      (node (ref "U$10") (pin "2") (pinfunction "CKI_2") (pintype "bidirectional"))
      (node (ref "U$9") (pin "5") (pinfunction "CKO_5") (pintype "bidirectional"))
    )
    (net (code "52") (name "Net-(U$10-CKO)") (class "Default")
      (node (ref "U$10") (pin "5") (pinfunction "CKO_5") (pintype "bidirectional"))
      (node (ref "U$11") (pin "2") (pinfunction "CKI_2") (pintype "bidirectional"))
    )
    (net (code "53") (name "Net-(U$10-SDI)") (class "Default")
      (node (ref "U$10") (pin "1") (pinfunction "SDI_1") (pintype "bidirectional"))
      (node (ref "U$9") (pin "6") (pinfunction "SDO_6") (pintype "bidirectional"))
    )
    (net (code "54") (name "Net-(U$10-SDO)") (class "Default")
      (node (ref "U$10") (pin "6") (pinfunction "SDO_6") (pintype "bidirectional"))
      (node (ref "U$11") (pin "1") (pinfunction "SDI_1") (pintype "bidirectional"))
    )
    (net (code "55") (name "Net-(U$11-CKO)") (class "Default")
      (node (ref "U$11") (pin "5") (pinfunction "CKO_5") (pintype "bidirectional"))
      (node (ref "U$13") (pin "2") (pinfunction "CKI_2") (pintype "bidirectional"))
    )
    (net (code "56") (name "Net-(U$11-SDO)") (class "Default")
      (node (ref "U$11") (pin "6") (pinfunction "SDO_6") (pintype "bidirectional"))
      (node (ref "U$13") (pin "1") (pinfunction "SDI_1") (pintype "bidirectional"))
    )
    (net (code "57") (name "Net-(U$13-CKO)") (class "Default")
      (node (ref "U$13") (pin "5") (pinfunction "CKO_5") (pintype "bidirectional"))
      (node (ref "U$14") (pin "2") (pinfunction "CKI_2") (pintype "bidirectional"))
    )
    (net (code "58") (name "Net-(U$13-SDO)") (class "Default")
      (node (ref "U$13") (pin "6") (pinfunction "SDO_6") (pintype "bidirectional"))
      (node (ref "U$14") (pin "1") (pinfunction "SDI_1") (pintype "bidirectional"))
    )
    (net (code "59") (name "Net-(U$15-CKO)") (class "Default")
      (node (ref "U$15") (pin "5") (pinfunction "CKO_5") (pintype "bidirectional"))
      (node (ref "U$16") (pin "2") (pinfunction "CKI_2") (pintype "bidirectional"))
    )
    (net (code "60") (name "Net-(U$15-SDO)") (class "Default")
      (node (ref "U$15") (pin "6") (pinfunction "SDO_6") (pintype "bidirectional"))
      (node (ref "U$16") (pin "1") (pinfunction "SDI_1") (pintype "bidirectional"))
    )
    (net (code "61") (name "Net-(U$16-CKO)") (class "Default")
      (node (ref "U$16") (pin "5") (pinfunction "CKO_5") (pintype "bidirectional"))
      (node (ref "U$17") (pin "2") (pinfunction "CKI_2") (pintype "bidirectional"))
    )
    (net (code "62") (name "Net-(U$16-SDO)") (class "Default")
      (node (ref "U$16") (pin "6") (pinfunction "SDO_6") (pintype "bidirectional"))
      (node (ref "U$17") (pin "1") (pinfunction "SDI_1") (pintype "bidirectional"))
    )
    (net (code "63") (name "Net-(U$17-CKO)") (class "Default")
      (node (ref "U$17") (pin "5") (pinfunction "CKO_5") (pintype "bidirectional"))
      (node (ref "U$18") (pin "2") (pinfunction "CKI_2") (pintype "bidirectional"))
    )
    (net (code "64") (name "Net-(U$17-SDO)") (class "Default")
      (node (ref "U$17") (pin "6") (pinfunction "SDO_6") (pintype "bidirectional"))
      (node (ref "U$18") (pin "1") (pinfunction "SDI_1") (pintype "bidirectional"))
    )
    (net (code "65") (name "Net-(U$18-CKO)") (class "Default")
      (node (ref "U$18") (pin "5") (pinfunction "CKO_5") (pintype "bidirectional"))
      (node (ref "U$19") (pin "2") (pinfunction "CKI_2") (pintype "bidirectional"))
    )
    (net (code "66") (name "Net-(U$18-SDO)") (class "Default")
      (node (ref "U$18") (pin "6") (pinfunction "SDO_6") (pintype "bidirectional"))
      (node (ref "U$19") (pin "1") (pinfunction "SDI_1") (pintype "bidirectional"))
    )
    (net (code "67") (name "Net-(U$19-CKO)") (class "Default")
      (node (ref "U$19") (pin "5") (pinfunction "CKO_5") (pintype "bidirectional"))
      (node (ref "U$20") (pin "2") (pinfunction "CKI_2") (pintype "bidirectional"))
    )
    (net (code "68") (name "Net-(U$19-SDO)") (class "Default")
      (node (ref "U$19") (pin "6") (pinfunction "SDO_6") (pintype "bidirectional"))
      (node (ref "U$20") (pin "1") (pinfunction "SDI_1") (pintype "bidirectional"))
    )
    (net (code "69") (name "Net-(U$20-CKO)") (class "Default")
      (node (ref "U$20") (pin "5") (pinfunction "CKO_5") (pintype "bidirectional"))
      (node (ref "U$21") (pin "2") (pinfunction "CKI_2") (pintype "bidirectional"))
    )
    (net (code "70") (name "Net-(U$20-SDO)") (class "Default")
      (node (ref "U$20") (pin "6") (pinfunction "SDO_6") (pintype "bidirectional"))
      (node (ref "U$21") (pin "1") (pinfunction "SDI_1") (pintype "bidirectional"))
    )
    (net (code "71") (name "Net-(U$21-CKO)") (class "Default")
      (node (ref "U$21") (pin "5") (pinfunction "CKO_5") (pintype "bidirectional"))
      (node (ref "U$22") (pin "2") (pinfunction "CKI_2") (pintype "bidirectional"))
    )
    (net (code "72") (name "Net-(U$21-SDO)") (class "Default")
      (node (ref "U$21") (pin "6") (pinfunction "SDO_6") (pintype "bidirectional"))
      (node (ref "U$22") (pin "1") (pinfunction "SDI_1") (pintype "bidirectional"))
    )
    (net (code "73") (name "Net-(U$22-CKO)") (class "Default")
      (node (ref "U$22") (pin "5") (pinfunction "CKO_5") (pintype "bidirectional"))
      (node (ref "U$23") (pin "2") (pinfunction "CKI_2") (pintype "bidirectional"))
    )
    (net (code "74") (name "Net-(U$22-SDO)") (class "Default")
      (node (ref "U$22") (pin "6") (pinfunction "SDO_6") (pintype "bidirectional"))
      (node (ref "U$23") (pin "1") (pinfunction "SDI_1") (pintype "bidirectional"))
    )
    (net (code "75") (name "Net-(U$23-CKO)") (class "Default")
      (node (ref "U$23") (pin "5") (pinfunction "CKO_5") (pintype "bidirectional"))
      (node (ref "U$24") (pin "2") (pinfunction "CKI_2") (pintype "bidirectional"))
    )
    (net (code "76") (name "Net-(U$23-SDO)") (class "Default")
      (node (ref "U$23") (pin "6") (pinfunction "SDO_6") (pintype "bidirectional"))
      (node (ref "U$24") (pin "1") (pinfunction "SDI_1") (pintype "bidirectional"))
    )
    (net (code "77") (name "Net-(U$24-CKO)") (class "Default")
      (node (ref "U$24") (pin "5") (pinfunction "CKO_5") (pintype "bidirectional"))
      (node (ref "U$25") (pin "2") (pinfunction "CKI_2") (pintype "bidirectional"))
    )
    (net (code "78") (name "Net-(U$24-SDO)") (class "Default")
      (node (ref "U$24") (pin "6") (pinfunction "SDO_6") (pintype "bidirectional"))
      (node (ref "U$25") (pin "1") (pinfunction "SDI_1") (pintype "bidirectional"))
    )
    (net (code "79") (name "Net-(U$25-CKO)") (class "Default")
      (node (ref "U$25") (pin "5") (pinfunction "CKO_5") (pintype "bidirectional"))
      (node (ref "U$26") (pin "2") (pinfunction "CKI_2") (pintype "bidirectional"))
    )
    (net (code "80") (name "Net-(U$25-SDO)") (class "Default")
      (node (ref "U$25") (pin "6") (pinfunction "SDO_6") (pintype "bidirectional"))
      (node (ref "U$26") (pin "1") (pinfunction "SDI_1") (pintype "bidirectional"))
    )
    (net (code "81") (name "Net-(U$26-CKO)") (class "Default")
      (node (ref "U$26") (pin "5") (pinfunction "CKO_5") (pintype "bidirectional"))
      (node (ref "U$27") (pin "2") (pinfunction "CKI_2") (pintype "bidirectional"))
    )
    (net (code "82") (name "Net-(U$26-SDO)") (class "Default")
      (node (ref "U$26") (pin "6") (pinfunction "SDO_6") (pintype "bidirectional"))
      (node (ref "U$27") (pin "1") (pinfunction "SDI_1") (pintype "bidirectional"))
    )
    (net (code "83") (name "VCC") (class "Default")
      (node (ref "C1") (pin "1") (pinfunction "1_1") (pintype "passive"))
      (node (ref "C2") (pin "1") (pinfunction "1_1") (pintype "passive"))
      (node (ref "C3") (pin "1") (pinfunction "1_1") (pintype "passive"))
      (node (ref "C4") (pin "1") (pinfunction "1_1") (pintype "passive"))
      (node (ref "C5") (pin "1") (pinfunction "1_1") (pintype "passive"))
      (node (ref "C6") (pin "1") (pinfunction "1_1") (pintype "passive"))
      (node (ref "C7") (pin "1") (pinfunction "1_1") (pintype "passive"))
      (node (ref "C8") (pin "1") (pinfunction "1_1") (pintype "passive"))
      (node (ref "C9") (pin "1") (pinfunction "1_1") (pintype "passive"))
      (node (ref "U$1") (pin "2") (pinfunction "2_2") (pintype "bidirectional"))
      (node (ref "U$10") (pin "4") (pinfunction "VCC_4") (pintype "power_in"))
      (node (ref "U$11") (pin "4") (pinfunction "VCC_4") (pintype "power_in"))
      (node (ref "U$13") (pin "4") (pinfunction "VCC_4") (pintype "power_in"))
      (node (ref "U$14") (pin "4") (pinfunction "VCC_4") (pintype "power_in"))
      (node (ref "U$15") (pin "4") (pinfunction "VCC_4") (pintype "power_in"))
      (node (ref "U$16") (pin "4") (pinfunction "VCC_4") (pintype "power_in"))
      (node (ref "U$17") (pin "4") (pinfunction "VCC_4") (pintype "power_in"))
      (node (ref "U$18") (pin "4") (pinfunction "VCC_4") (pintype "power_in"))
      (node (ref "U$19") (pin "4") (pinfunction "VCC_4") (pintype "power_in"))
      (node (ref "U$2") (pin "4") (pinfunction "VCC_4") (pintype "power_in"))
      (node (ref "U$20") (pin "4") (pinfunction "VCC_4") (pintype "power_in"))
      (node (ref "U$21") (pin "4") (pinfunction "VCC_4") (pintype "power_in"))
      (node (ref "U$22") (pin "4") (pinfunction "VCC_4") (pintype "power_in"))
      (node (ref "U$23") (pin "4") (pinfunction "VCC_4") (pintype "power_in"))
      (node (ref "U$24") (pin "4") (pinfunction "VCC_4") (pintype "power_in"))
      (node (ref "U$25") (pin "4") (pinfunction "VCC_4") (pintype "power_in"))
      (node (ref "U$26") (pin "4") (pinfunction "VCC_4") (pintype "power_in"))
      (node (ref "U$27") (pin "4") (pinfunction "VCC_4") (pintype "power_in"))
      (node (ref "U$3") (pin "4") (pinfunction "VCC_4") (pintype "power_in"))
      (node (ref "U$4") (pin "4") (pinfunction "VCC_4") (pintype "power_in"))
      (node (ref "U$5") (pin "4") (pinfunction "VCC_4") (pintype "power_in"))
      (node (ref "U$6") (pin "4") (pinfunction "VCC_4") (pintype "power_in"))
      (node (ref "U$7") (pin "4") (pinfunction "VCC_4") (pintype "power_in"))
      (node (ref "U$8") (pin "4") (pinfunction "VCC_4") (pintype "power_in"))
      (node (ref "U$9") (pin "4") (pinfunction "VCC_4") (pintype "power_in"))
    )
    (net (code "84") (name "unconnected-(U$27-CKO-Pad5)") (class "Default")
      (node (ref "U$27") (pin "5") (pinfunction "CKO_5") (pintype "bidirectional"))
    )
    (net (code "85") (name "unconnected-(U$27-SDO-Pad6)") (class "Default")
      (node (ref "U$27") (pin "6") (pinfunction "SDO_6") (pintype "bidirectional"))
    )
  )
)
